# vcp.net
KiCad netlist of a schematic drawn in Altium Designer
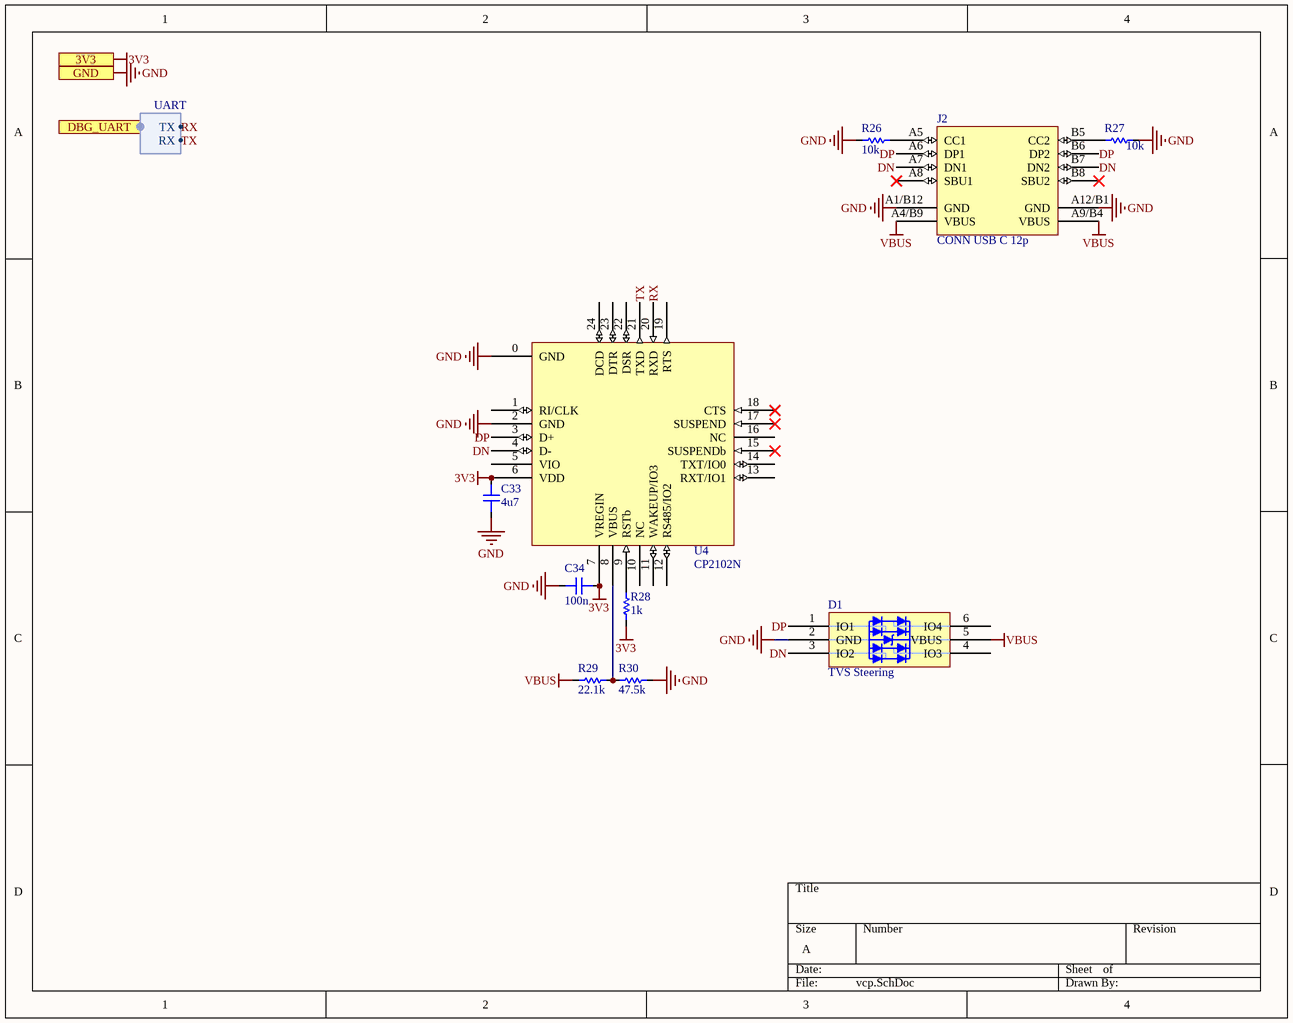
[diagram p0: vcp.SchDoc]

(export (version "E")
  (design (tool "Eeschema 10.0.6"))
  (components
    (comp (ref "C33")
      (value "4u7")
      (footprint "CAP 0805 L")
      (description "CAP 0805")
      (libsource (lib "streetbot") (part "CAP 0805"))
    )
    (comp (ref "C34")
      (value "100n")
      (footprint "CAP 0805 L")
      (description "CAP 0805")
      (libsource (lib "streetbot") (part "CAP 0805"))
    )
    (comp (ref "D1")
      (value "TVS Steering")
      (footprint "SC-74")
      (description "CM1293A-04SO")
      (libsource (lib "streetbot") (part "DTVS 2Rail 4x"))
    )
    (comp (ref "J2")
      (value "CONN USB C 12p")
      (footprint "CONN USB C 12P")
      (description "USB - Type C Female 12 SMD USB Connectors RoHS")
      (fields (field (name "LCSC PART #") "C167321"))
      (libsource (lib "streetbot") (part "CONN USB C 12p"))
    )
    (comp (ref "R26")
      (value "10k")
      (footprint "RES 0603 L")
      (description "RES 0603")
      (libsource (lib "streetbot") (part "RES 0603"))
    )
    (comp (ref "R27")
      (value "10k")
      (footprint "RES 0603 L")
      (description "RES 0603")
      (libsource (lib "streetbot") (part "RES 0603"))
    )
    (comp (ref "R28")
      (value "1k")
      (footprint "RES 0603 L")
      (description "RES 0603")
      (libsource (lib "streetbot") (part "RES 0603"))
    )
    (comp (ref "R29")
      (value "22.1k")
      (footprint "RES 0603 L")
      (description "RES 0603")
      (libsource (lib "streetbot") (part "RES 0603"))
    )
    (comp (ref "R30")
      (value "47.5k")
      (footprint "RES 0603 L")
      (description "RES 0603")
      (libsource (lib "streetbot") (part "RES 0603"))
    )
    (comp (ref "U4")
      (value "CP2102N")
      (footprint "VQFN24")
      (libsource (lib "streetbot") (part "IC USB UART CP2102N"))
    )
  )
  (nets
    (net (code "2") (name "/DN") (class "Default")
      (node (ref "D1") (pin "3") (pinfunction "IO2_3") (pintype "passive"))
      (node (ref "J2") (pin "A7") (pinfunction "DN1_A7") (pintype "bidirectional"))
      (node (ref "J2") (pin "B7") (pinfunction "DN2_B7") (pintype "bidirectional"))
      (node (ref "U4") (pin "4") (pinfunction "D-_4") (pintype "bidirectional"))
    )
    (net (code "3") (name "/DP") (class "Default")
      (node (ref "D1") (pin "1") (pinfunction "IO1_1") (pintype "passive"))
      (node (ref "J2") (pin "A6") (pinfunction "DP1_A6") (pintype "bidirectional"))
      (node (ref "J2") (pin "B6") (pinfunction "DP2_B6") (pintype "bidirectional"))
      (node (ref "U4") (pin "3") (pinfunction "D+_3") (pintype "bidirectional"))
    )
    (net (code "4") (name "/RX") (class "Default")
      (node (ref "U4") (pin "20") (pinfunction "RXD_20") (pintype "input"))
    )
    (net (code "5") (name "/TX") (class "Default")
      (node (ref "U4") (pin "21") (pinfunction "TXD_21") (pintype "output"))
    )
    (net (code "7") (name "3V3") (class "Default")
      (node (ref "C33") (pin "2") (pinfunction "2_2") (pintype "passive"))
      (node (ref "C34") (pin "2") (pinfunction "2_2") (pintype "passive"))
      (node (ref "R28") (pin "1") (pinfunction "1_1") (pintype "passive"))
      (node (ref "U4") (pin "6") (pinfunction "VDD_6") (pintype "power_in"))
      (node (ref "U4") (pin "7") (pinfunction "VREGIN_7") (pintype "power_in"))
    )
    (net (code "8") (name "GND") (class "Default")
      (node (ref "C33") (pin "1") (pinfunction "1_1") (pintype "passive"))
      (node (ref "C34") (pin "1") (pinfunction "1_1") (pintype "passive"))
      (node (ref "D1") (pin "2") (pinfunction "GND_2") (pintype "passive"))
      (node (ref "J2") (pin "A1/B12") (pinfunction "GND_A1/B12") (pintype "power_in"))
      (node (ref "J2") (pin "A12/B1") (pinfunction "GND_A12/B1") (pintype "power_in"))
      (node (ref "R26") (pin "2") (pinfunction "2_2") (pintype "passive"))
      (node (ref "R27") (pin "1") (pinfunction "1_1") (pintype "passive"))
      (node (ref "R30") (pin "2") (pinfunction "2_2") (pintype "passive"))
      (node (ref "U4") (pin "0") (pinfunction "GND_0") (pintype "power_in"))
      (node (ref "U4") (pin "2") (pinfunction "GND_2") (pintype "power_in"))
    )
    (net (code "9") (name "Net-(J2-CC1)") (class "Default")
      (node (ref "J2") (pin "A5") (pinfunction "CC1_A5") (pintype "bidirectional"))
      (node (ref "R26") (pin "1") (pinfunction "1_1") (pintype "passive"))
    )
    (net (code "10") (name "Net-(J2-CC2)") (class "Default")
      (node (ref "J2") (pin "B5") (pinfunction "CC2_B5") (pintype "bidirectional"))
      (node (ref "R27") (pin "2") (pinfunction "2_2") (pintype "passive"))
    )
    (net (code "11") (name "Net-(U4-RSTb)") (class "Default")
      (node (ref "R28") (pin "2") (pinfunction "2_2") (pintype "passive"))
      (node (ref "U4") (pin "9") (pinfunction "RSTb_9") (pintype "input"))
    )
    (net (code "12") (name "Net-(U4-VBUS)") (class "Default")
      (node (ref "R29") (pin "2") (pinfunction "2_2") (pintype "passive"))
      (node (ref "R30") (pin "1") (pinfunction "1_1") (pintype "passive"))
      (node (ref "U4") (pin "8") (pinfunction "VBUS_8") (pintype "power_in"))
    )
    (net (code "13") (name "VBUS") (class "Default")
      (node (ref "D1") (pin "5") (pinfunction "VBUS_5") (pintype "passive"))
      (node (ref "J2") (pin "A4/B9") (pinfunction "VBUS_A4/B9") (pintype "power_in"))
      (node (ref "J2") (pin "A9/B4") (pinfunction "VBUS_A9/B4") (pintype "power_in"))
      (node (ref "R29") (pin "1") (pinfunction "1_1") (pintype "passive"))
    )
    (net (code "14") (name "unconnected-(D1-IO3-Pad4)") (class "Default")
      (node (ref "D1") (pin "4") (pinfunction "IO3_4") (pintype "passive"))
    )
    (net (code "15") (name "unconnected-(D1-IO4-Pad6)") (class "Default")
      (node (ref "D1") (pin "6") (pinfunction "IO4_6") (pintype "passive"))
    )
    (net (code "16") (name "unconnected-(J2-SBU1-PadA8)") (class "Default")
      (node (ref "J2") (pin "A8") (pinfunction "SBU1_A8") (pintype "bidirectional+no_connect"))
    )
    (net (code "17") (name "unconnected-(J2-SBU2-PadB8)") (class "Default")
      (node (ref "J2") (pin "B8") (pinfunction "SBU2_B8") (pintype "bidirectional+no_connect"))
    )
    (net (code "18") (name "unconnected-(U4-CTS-Pad18)") (class "Default")
      (node (ref "U4") (pin "18") (pinfunction "CTS_18") (pintype "input+no_connect"))
    )
    (net (code "19") (name "unconnected-(U4-DCD-Pad24)") (class "Default")
      (node (ref "U4") (pin "24") (pinfunction "DCD_24") (pintype "bidirectional"))
    )
    (net (code "20") (name "unconnected-(U4-DSR-Pad22)") (class "Default")
      (node (ref "U4") (pin "22") (pinfunction "DSR_22") (pintype "bidirectional"))
    )
    (net (code "21") (name "unconnected-(U4-DTR-Pad23)") (class "Default")
      (node (ref "U4") (pin "23") (pinfunction "DTR_23") (pintype "bidirectional"))
    )
    (net (code "22") (name "unconnected-(U4-NC-Pad10)") (class "Default")
      (node (ref "U4") (pin "10") (pinfunction "NC_10") (pintype "passive"))
    )
    (net (code "23") (name "unconnected-(U4-NC-Pad16)") (class "Default")
      (node (ref "U4") (pin "16") (pinfunction "NC_16") (pintype "passive"))
    )
    (net (code "24") (name "unconnected-(U4-RI{slash}CLK-Pad1)") (class "Default")
      (node (ref "U4") (pin "1") (pinfunction "RI/CLK_1") (pintype "bidirectional"))
    )
    (net (code "25") (name "unconnected-(U4-RS485{slash}IO2-Pad12)") (class "Default")
      (node (ref "U4") (pin "12") (pinfunction "RS485/IO2_12") (pintype "bidirectional"))
    )
    (net (code "26") (name "unconnected-(U4-RTS-Pad19)") (class "Default")
      (node (ref "U4") (pin "19") (pinfunction "RTS_19") (pintype "output"))
    )
    (net (code "27") (name "unconnected-(U4-RXT{slash}IO1-Pad13)") (class "Default")
      (node (ref "U4") (pin "13") (pinfunction "RXT/IO1_13") (pintype "bidirectional"))
    )
    (net (code "28") (name "unconnected-(U4-SUSPEND-Pad17)") (class "Default")
      (node (ref "U4") (pin "17") (pinfunction "SUSPEND_17") (pintype "input+no_connect"))
    )
    (net (code "29") (name "unconnected-(U4-SUSPENDb-Pad15)") (class "Default")
      (node (ref "U4") (pin "15") (pinfunction "SUSPENDb_15") (pintype "input+no_connect"))
    )
    (net (code "30") (name "unconnected-(U4-TXT{slash}IO0-Pad14)") (class "Default")
      (node (ref "U4") (pin "14") (pinfunction "TXT/IO0_14") (pintype "bidirectional"))
    )
    (net (code "31") (name "unconnected-(U4-VIO-Pad5)") (class "Default")
      (node (ref "U4") (pin "5") (pinfunction "VIO_5") (pintype "power_in"))
    )
    (net (code "32") (name "unconnected-(U4-WAKEUP{slash}IO3-Pad11)") (class "Default")
      (node (ref "U4") (pin "11") (pinfunction "WAKEUP/IO3_11") (pintype "bidirectional"))
    )
  )
)
